# ProProject_TLE5012B_8pin_2024-05-29.net
KiCad netlist of a schematic drawn in EasyEDA Pro
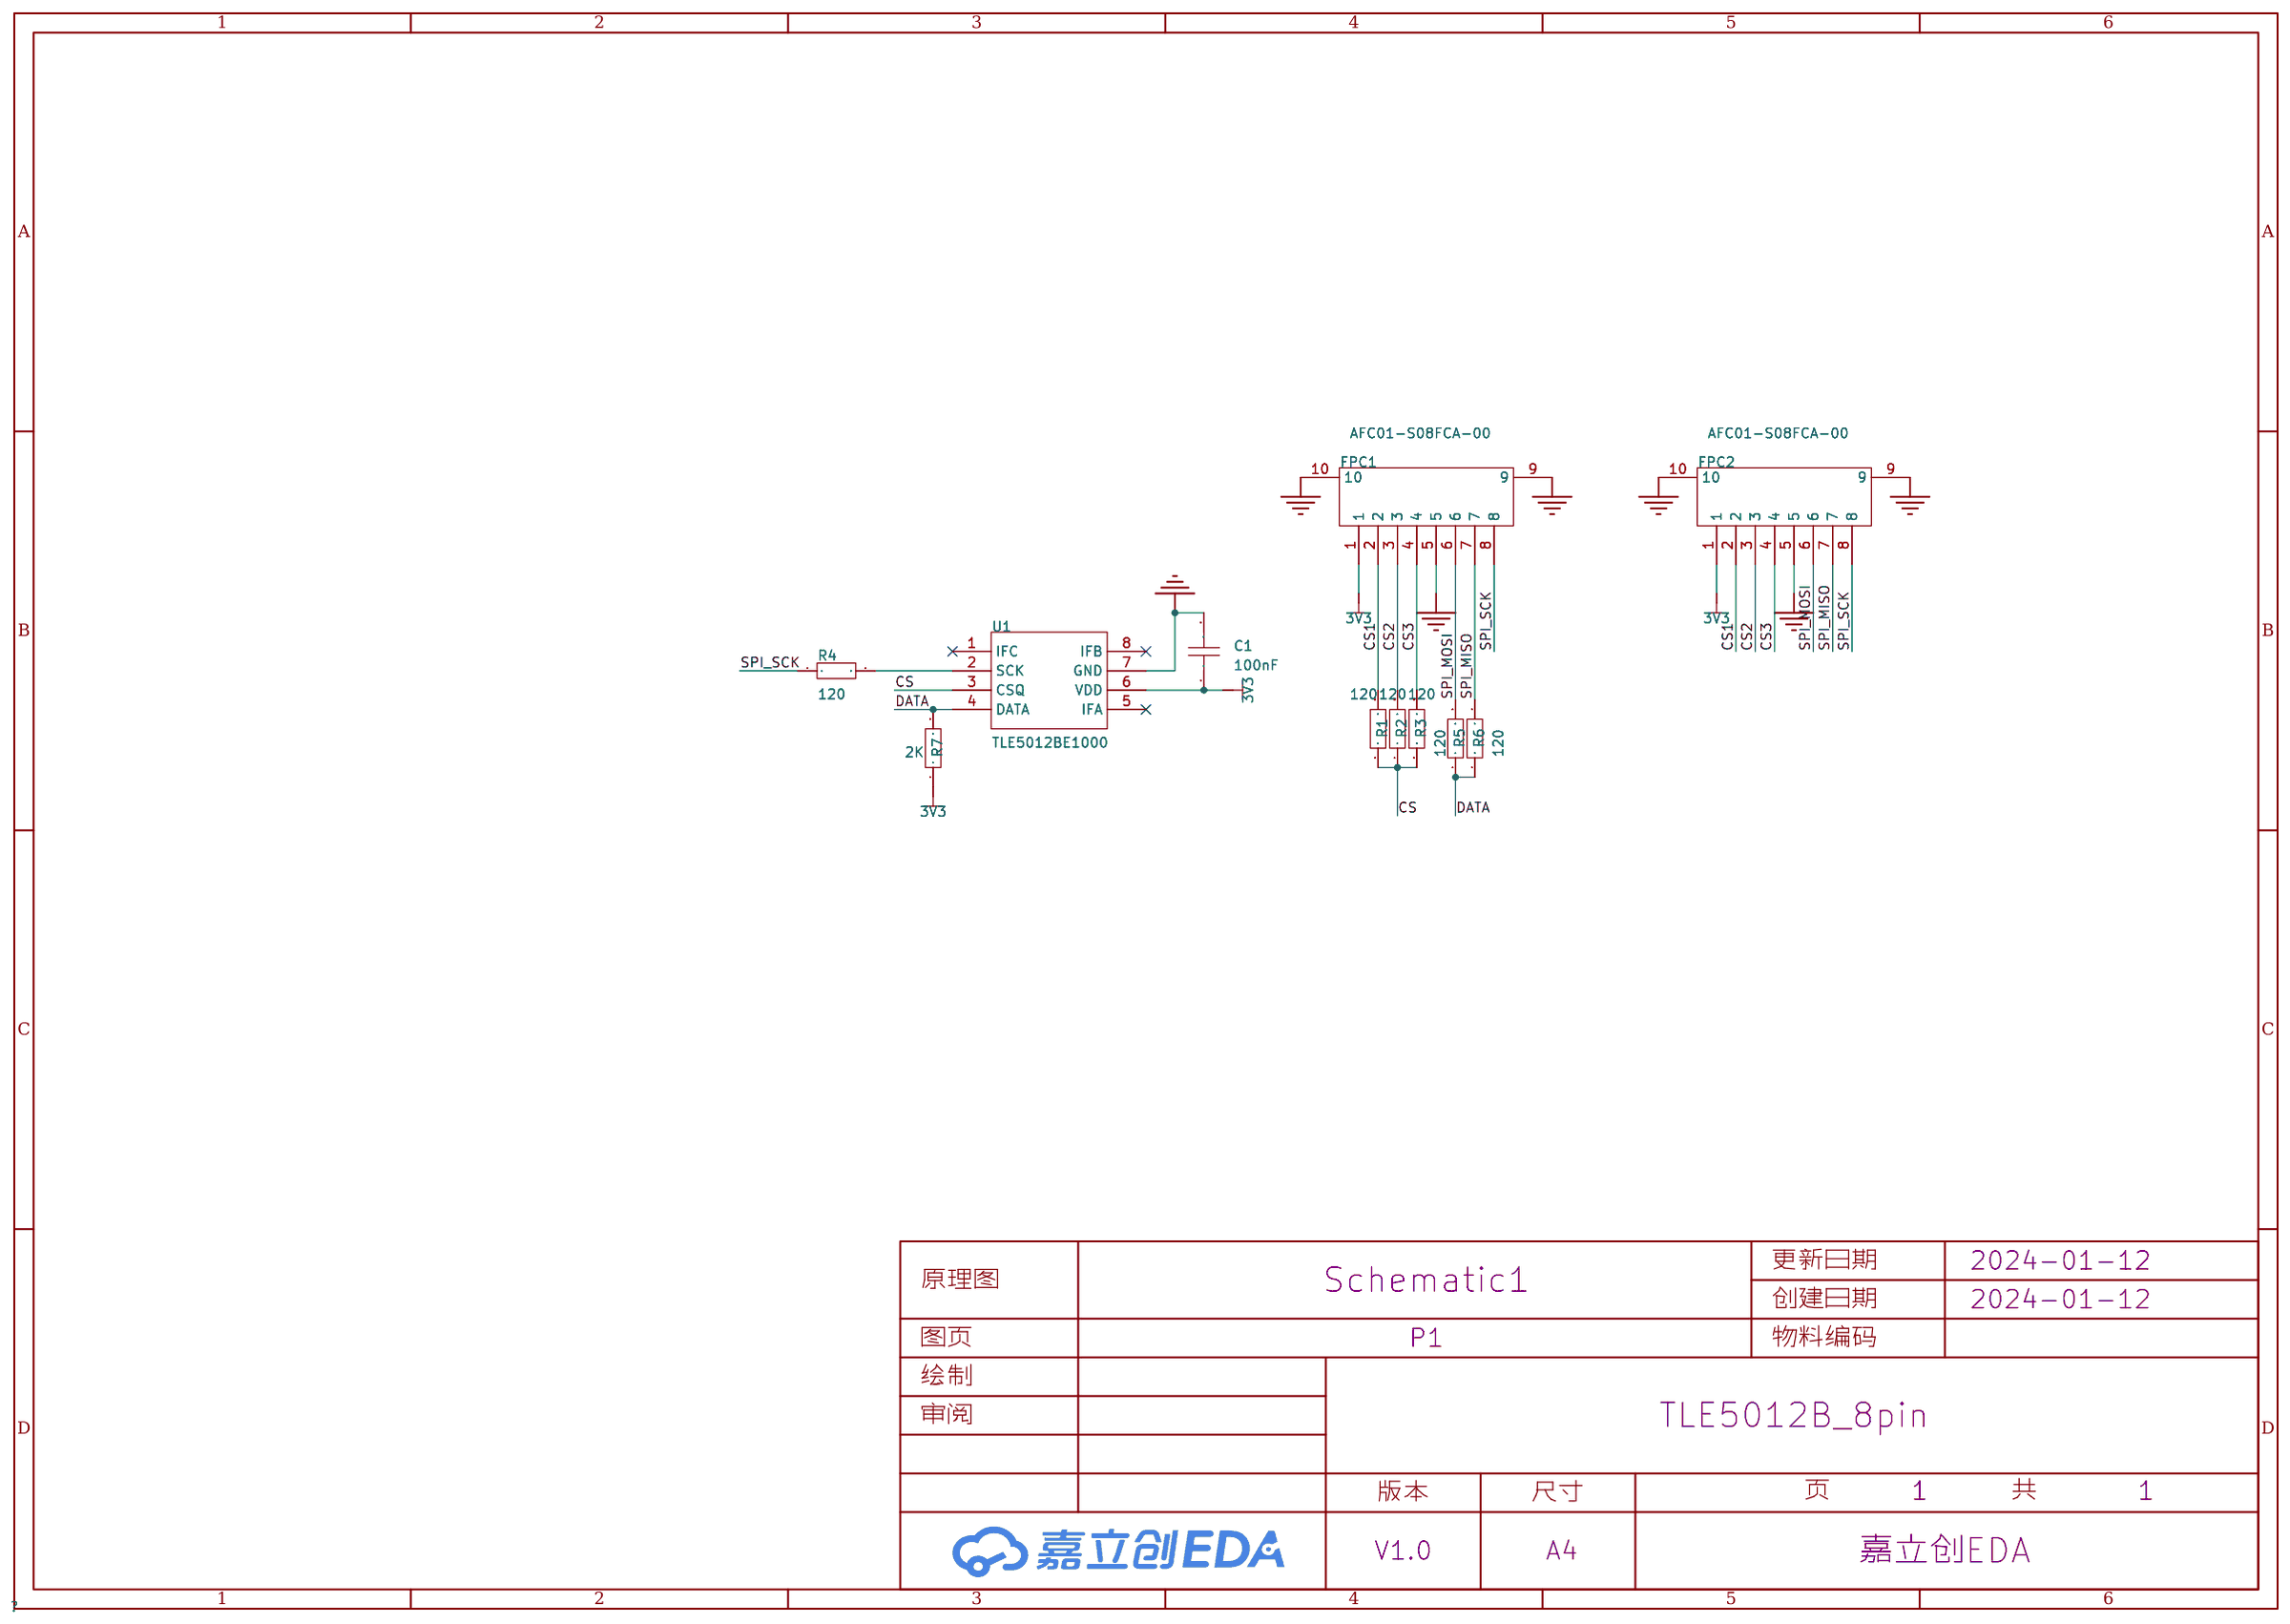
[diagram p0: schematic sheet]

(export (version "E")
  (design (tool "Eeschema 10.0.6"))
  (components
    (comp (ref "C1")
      (value "100nF")
      (footprint "easyedapro:C0402")
      (libsource (lib "easyedapro") (part "CapAcitance"))
    )
    (comp (ref "FPC1")
      (value "AFC01-S08FCA-00")
      (footprint "easyedapro:FPC-SMD_P0.50-8P_FGS-XJ-H2.0")
      (description "间距:0.5mm;触点数量:8P;锁定特性:翻盖式;触点类型:下接;安装类型:卧贴;")
      (fields (field (name "Manufacturer") "JS(钜硕电子)"))
      (libsource (lib "easyedapro") (part "AFC01-S08FCA-00"))
    )
    (comp (ref "FPC2")
      (value "AFC01-S08FCA-00")
      (footprint "easyedapro:FPC-SMD_P0.50-8P_FGS-XJ-H2.0")
      (description "间距:0.5mm;触点数量:8P;锁定特性:翻盖式;触点类型:下接;安装类型:卧贴;")
      (fields (field (name "Manufacturer") "JS(钜硕电子)"))
      (libsource (lib "easyedapro") (part "AFC01-S08FCA-00"))
    )
    (comp (ref "R1") (value "120") (footprint "easyedapro:R0402") (libsource (lib "easyedapro") (part "电阻")))
    (comp (ref "R2") (value "120") (footprint "easyedapro:R0402") (libsource (lib "easyedapro") (part "电阻")))
    (comp (ref "R3") (value "120") (footprint "easyedapro:R0402") (libsource (lib "easyedapro") (part "电阻")))
    (comp (ref "R4") (value "120") (footprint "easyedapro:R0402") (libsource (lib "easyedapro") (part "电阻")))
    (comp (ref "R5") (value "120") (footprint "easyedapro:R0402") (libsource (lib "easyedapro") (part "电阻")))
    (comp (ref "R6") (value "120") (footprint "easyedapro:R0402") (libsource (lib "easyedapro") (part "电阻")))
    (comp (ref "R7") (value "2K") (footprint "easyedapro:R0402") (libsource (lib "easyedapro") (part "电阻")))
    (comp (ref "U1")
      (value "TLE5012BE1000")
      (footprint "easyedapro:PG-DSO-8_L5.0-W4.0-P1.27-LS6.0-BL")
      (description "采用巨磁电阻的角度传感器")
      (fields (field (name "Manufacturer") "Infineon(英飞凌)"))
      (libsource (lib "easyedapro") (part "TLE5012BE1000XUMA1"))
    )
  )
  (nets
    (net (code "1") (name "/CS") (class "Default")
      (node (ref "R1") (pin "1") (pinfunction "1_1") (pintype "input"))
      (node (ref "R2") (pin "1") (pinfunction "1_1") (pintype "input"))
      (node (ref "R3") (pin "1") (pinfunction "1_1") (pintype "input"))
      (node (ref "U1") (pin "3") (pinfunction "CSQ_3") (pintype "unspecified"))
    )
    (net (code "2") (name "/CS1") (class "Default")
      (node (ref "FPC1") (pin "2") (pinfunction "2_2") (pintype "unspecified"))
      (node (ref "FPC2") (pin "2") (pinfunction "2_2") (pintype "unspecified"))
      (node (ref "R1") (pin "2") (pinfunction "2_2") (pintype "input"))
    )
    (net (code "3") (name "/CS2") (class "Default")
      (node (ref "FPC1") (pin "3") (pinfunction "3_3") (pintype "unspecified"))
      (node (ref "FPC2") (pin "3") (pinfunction "3_3") (pintype "unspecified"))
      (node (ref "R2") (pin "2") (pinfunction "2_2") (pintype "input"))
    )
    (net (code "4") (name "/CS3") (class "Default")
      (node (ref "FPC1") (pin "4") (pinfunction "4_4") (pintype "unspecified"))
      (node (ref "FPC2") (pin "4") (pinfunction "4_4") (pintype "unspecified"))
      (node (ref "R3") (pin "2") (pinfunction "2_2") (pintype "input"))
    )
    (net (code "5") (name "/DATA") (class "Default")
      (node (ref "R5") (pin "1") (pinfunction "1_1") (pintype "input"))
      (node (ref "R6") (pin "1") (pinfunction "1_1") (pintype "input"))
      (node (ref "R7") (pin "2") (pinfunction "2_2") (pintype "input"))
      (node (ref "U1") (pin "4") (pinfunction "DATA_4") (pintype "unspecified"))
    )
    (net (code "6") (name "/SPI_MISO") (class "Default")
      (node (ref "FPC1") (pin "7") (pinfunction "7_7") (pintype "unspecified"))
      (node (ref "FPC2") (pin "7") (pinfunction "7_7") (pintype "unspecified"))
      (node (ref "R6") (pin "2") (pinfunction "2_2") (pintype "input"))
    )
    (net (code "7") (name "/SPI_MOSI") (class "Default")
      (node (ref "FPC1") (pin "6") (pinfunction "6_6") (pintype "unspecified"))
      (node (ref "FPC2") (pin "6") (pinfunction "6_6") (pintype "unspecified"))
      (node (ref "R5") (pin "2") (pinfunction "2_2") (pintype "input"))
    )
    (net (code "8") (name "/SPI_SCK") (class "Default")
      (node (ref "FPC1") (pin "8") (pinfunction "8_8") (pintype "unspecified"))
      (node (ref "FPC2") (pin "8") (pinfunction "8_8") (pintype "unspecified"))
      (node (ref "R4") (pin "1") (pinfunction "1_1") (pintype "input"))
    )
    (net (code "9") (name "3V3") (class "Default")
      (node (ref "C1") (pin "1") (pinfunction "1_1") (pintype "input"))
      (node (ref "FPC1") (pin "1") (pinfunction "1_1") (pintype "unspecified"))
      (node (ref "FPC2") (pin "1") (pinfunction "1_1") (pintype "unspecified"))
      (node (ref "R7") (pin "1") (pinfunction "1_1") (pintype "input"))
      (node (ref "U1") (pin "6") (pinfunction "VDD_6") (pintype "unspecified"))
    )
    (net (code "10") (name "GND") (class "Default")
      (node (ref "C1") (pin "2") (pinfunction "2_2") (pintype "input"))
      (node (ref "FPC1") (pin "10") (pinfunction "10_10") (pintype "unspecified"))
      (node (ref "FPC1") (pin "5") (pinfunction "5_5") (pintype "unspecified"))
      (node (ref "FPC1") (pin "9") (pinfunction "9_9") (pintype "unspecified"))
      (node (ref "FPC2") (pin "10") (pinfunction "10_10") (pintype "unspecified"))
      (node (ref "FPC2") (pin "5") (pinfunction "5_5") (pintype "unspecified"))
      (node (ref "FPC2") (pin "9") (pinfunction "9_9") (pintype "unspecified"))
      (node (ref "U1") (pin "7") (pinfunction "GND_7") (pintype "unspecified"))
    )
    (net (code "11") (name "Net-(U1-SCK)") (class "Default")
      (node (ref "R4") (pin "2") (pinfunction "2_2") (pintype "input"))
      (node (ref "U1") (pin "2") (pinfunction "SCK_2") (pintype "unspecified"))
    )
    (net (code "12") (name "unconnected-(U1-IFA-Pad5)") (class "Default")
      (node (ref "U1") (pin "5") (pinfunction "IFA_5") (pintype "unspecified+no_connect"))
    )
    (net (code "13") (name "unconnected-(U1-IFB-Pad8)") (class "Default")
      (node (ref "U1") (pin "8") (pinfunction "IFB_8") (pintype "unspecified+no_connect"))
    )
    (net (code "14") (name "unconnected-(U1-IFC-Pad1)") (class "Default")
      (node (ref "U1") (pin "1") (pinfunction "IFC_1") (pintype "unspecified+no_connect"))
    )
  )
)
